# carcomputer2.net
KiCad netlist of a schematic drawn in EAGLE
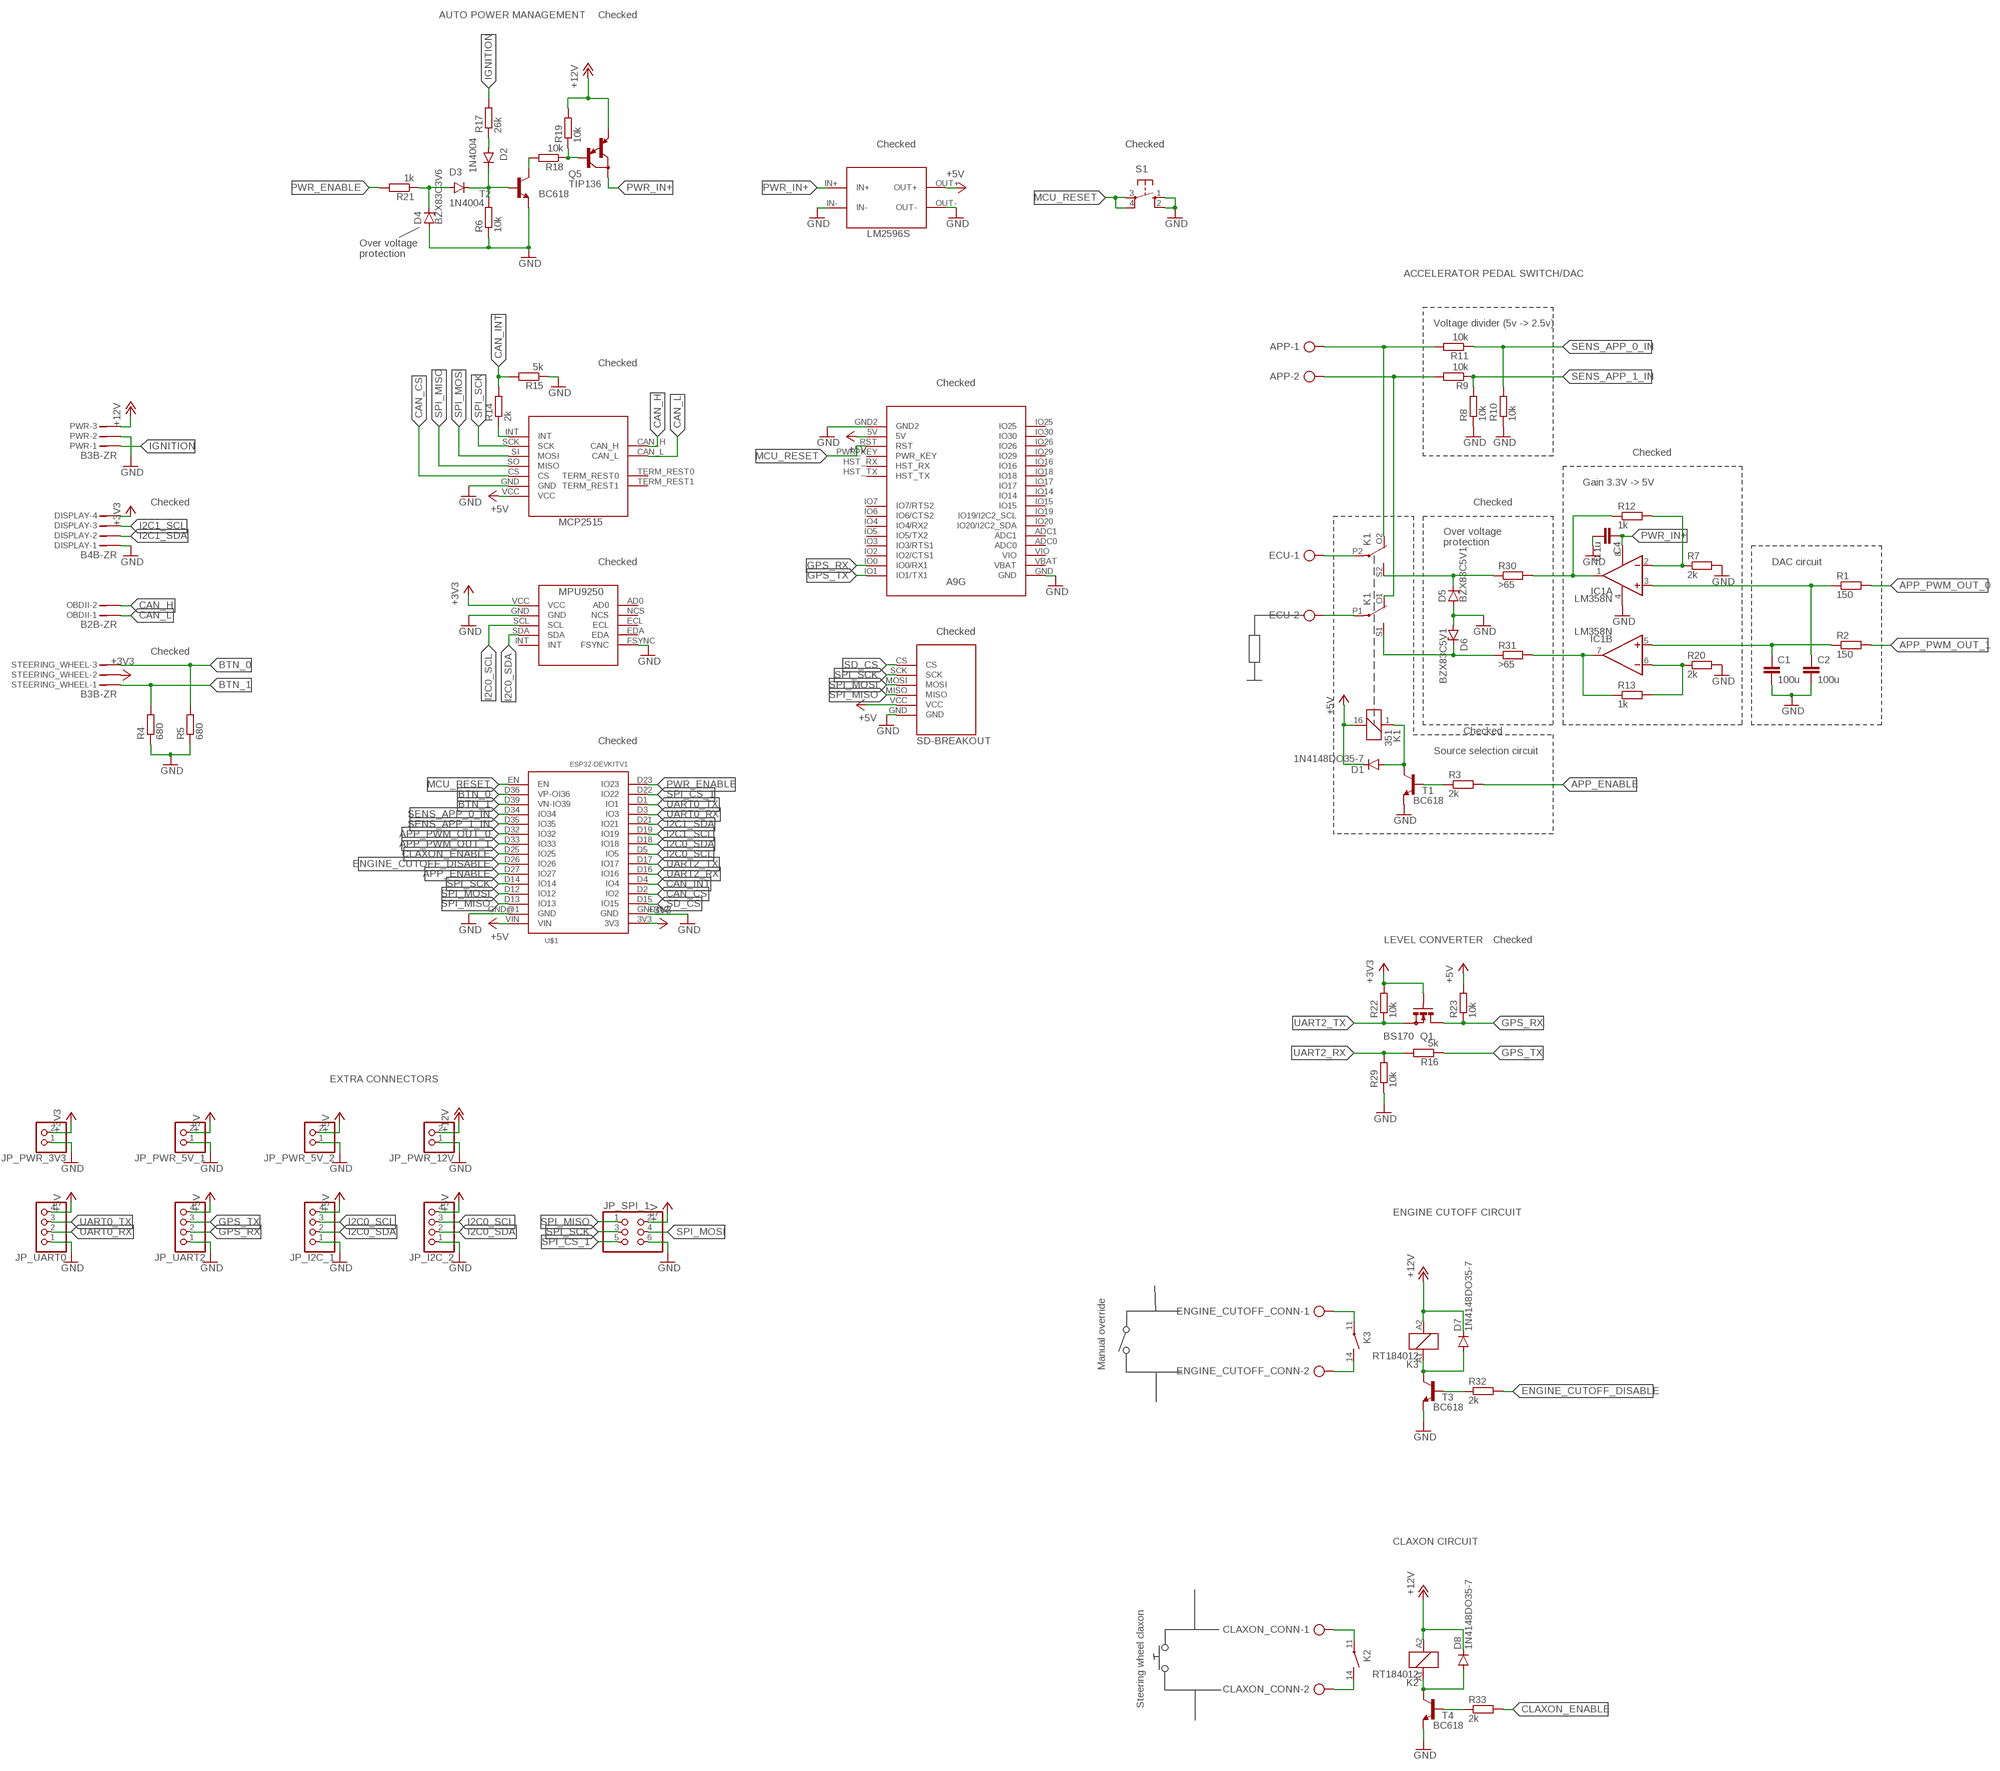
[diagram p0: schematic, sheet 1]

(export (version "E")
  (design (tool "Eeschema 10.0.6"))
  (components
    (comp (ref "APP")
      (value "AK300/2")
      (footprint "eagle-import:AK300_2")
      (libsource (lib "eagle-import") (part "AK300/2"))
    )
    (comp (ref "C1")
      (value "100u")
      (footprint "eagle-import:C025-050X050")
      (libsource (lib "eagle-import") (part "C-EU025-050X050"))
    )
    (comp (ref "C2")
      (value "100u")
      (footprint "eagle-import:C025-050X050")
      (libsource (lib "eagle-import") (part "C-EU025-050X050"))
    )
    (comp (ref "C4")
      (value "0.1u")
      (footprint "eagle-import:C025-050X050")
      (libsource (lib "eagle-import") (part "C-EU025-050X050"))
    )
    (comp (ref "CLAXON_CONN")
      (value "AK300/2")
      (footprint "eagle-import:AK300_2")
      (libsource (lib "eagle-import") (part "AK300/2"))
    )
    (comp (ref "D1")
      (value "1N4148DO35-7")
      (footprint "eagle-import:DO35-7")
      (libsource (lib "eagle-import") (part "1N4148DO35-7"))
    )
    (comp (ref "D2")
      (value "1N4004")
      (footprint "eagle-import:DO41-10")
      (libsource (lib "eagle-import") (part "1N4004"))
    )
    (comp (ref "D3")
      (value "1N4004")
      (footprint "eagle-import:DO41-10")
      (libsource (lib "eagle-import") (part "1N4004"))
    )
    (comp (ref "D4")
      (value "BZX83C3V6")
      (footprint "eagle-import:DO41Z10")
      (libsource (lib "eagle-import") (part "BZX85"))
    )
    (comp (ref "D5")
      (value "BZX83C5V1")
      (footprint "eagle-import:DO41Z10")
      (libsource (lib "eagle-import") (part "BZX85"))
    )
    (comp (ref "D6")
      (value "BZX83C5V1")
      (footprint "eagle-import:DO41Z10")
      (libsource (lib "eagle-import") (part "BZX85"))
    )
    (comp (ref "D7")
      (value "1N4148DO35-7")
      (footprint "eagle-import:DO35-7")
      (libsource (lib "eagle-import") (part "1N4148DO35-7"))
    )
    (comp (ref "D8")
      (value "1N4148DO35-7")
      (footprint "eagle-import:DO35-7")
      (libsource (lib "eagle-import") (part "1N4148DO35-7"))
    )
    (comp (ref "DISPLAY")
      (value "B4B-ZR")
      (footprint "eagle-import:B4B-ZR")
      (fields (field (name "MF") "FARNELL") (field (name "MPN") "B4B-ZR(LF)(SN)"))
      (libsource (lib "eagle-import") (part "?4B-ZRB"))
    )
    (comp (ref "ECU")
      (value "AK300/2")
      (footprint "eagle-import:AK300_2")
      (libsource (lib "eagle-import") (part "AK300/2"))
    )
    (comp (ref "ENGINE_CUTOFF_CONN")
      (value "AK300/2")
      (footprint "eagle-import:AK300_2")
      (libsource (lib "eagle-import") (part "AK300/2"))
    )
    (comp (ref "IC1")
      (value "LM358N")
      (footprint "eagle-import:DIL08")
      (libsource (lib "eagle-import") (part "LM358N"))
    )
    (comp (ref "JP_I2C_1")
      (value "PINHD-1X4")
      (footprint "eagle-import:1X04")
      (libsource (lib "eagle-import") (part "PINHD-1X4"))
    )
    (comp (ref "JP_I2C_2")
      (value "PINHD-1X4")
      (footprint "eagle-import:1X04")
      (libsource (lib "eagle-import") (part "PINHD-1X4"))
    )
    (comp (ref "JP_PWR_3V3")
      (value "PINHD-1X2")
      (footprint "eagle-import:1X02")
      (libsource (lib "eagle-import") (part "PINHD-1X2"))
    )
    (comp (ref "JP_PWR_5V_1")
      (value "PINHD-1X2")
      (footprint "eagle-import:1X02")
      (libsource (lib "eagle-import") (part "PINHD-1X2"))
    )
    (comp (ref "JP_PWR_5V_2")
      (value "PINHD-1X2")
      (footprint "eagle-import:1X02")
      (libsource (lib "eagle-import") (part "PINHD-1X2"))
    )
    (comp (ref "JP_PWR_12V")
      (value "PINHD-1X2")
      (footprint "eagle-import:1X02")
      (libsource (lib "eagle-import") (part "PINHD-1X2"))
    )
    (comp (ref "JP_SPI_1")
      (value "PINHD-2X3")
      (footprint "eagle-import:2X03")
      (libsource (lib "eagle-import") (part "PINHD-2X3"))
    )
    (comp (ref "JP_UART0")
      (value "PINHD-1X4")
      (footprint "eagle-import:1X04")
      (libsource (lib "eagle-import") (part "PINHD-1X4"))
    )
    (comp (ref "JP_UART2")
      (value "PINHD-1X4")
      (footprint "eagle-import:1X04")
      (libsource (lib "eagle-import") (part "PINHD-1X4"))
    )
    (comp (ref "K1")
      (value "351")
      (footprint "eagle-import:351")
      (libsource (lib "eagle-import") (part "351"))
    )
    (comp (ref "K2")
      (value "RT184012")
      (footprint "eagle-import:RT-N_O12A3.5")
      (fields (field (name "MF") "TYCO ELECTRONICS"))
      (libsource (lib "eagle-import") (part "RT?184012"))
    )
    (comp (ref "K3")
      (value "RT184012")
      (footprint "eagle-import:RT-N_O12A3.5")
      (fields (field (name "MF") "TYCO ELECTRONICS"))
      (libsource (lib "eagle-import") (part "RT?184012"))
    )
    (comp (ref "OBDII")
      (value "B2B-ZR")
      (footprint "eagle-import:B2B-ZR")
      (libsource (lib "eagle-import") (part "?2B-ZRB"))
    )
    (comp (ref "PWR")
      (value "B3B-ZR")
      (footprint "eagle-import:B3B-ZR")
      (libsource (lib "eagle-import") (part "?3B-ZRB"))
    )
    (comp (ref "Q1")
      (value "BS170")
      (footprint "eagle-import:SOT54E")
      (libsource (lib "eagle-import") (part "BS170"))
    )
    (comp (ref "Q5")
      (value "TIP136")
      (footprint "eagle-import:TO220")
      (libsource (lib "eagle-import") (part "TIP136"))
    )
    (comp (ref "R1")
      (value "150")
      (footprint "eagle-import:0207_7")
      (libsource (lib "eagle-import") (part "R-EU_0207/7"))
    )
    (comp (ref "R2")
      (value "150")
      (footprint "eagle-import:0207_7")
      (libsource (lib "eagle-import") (part "R-EU_0207/7"))
    )
    (comp (ref "R3")
      (value "2k")
      (footprint "eagle-import:0207_7")
      (libsource (lib "eagle-import") (part "R-EU_0207/7"))
    )
    (comp (ref "R4")
      (value "680")
      (footprint "eagle-import:0207_7")
      (libsource (lib "eagle-import") (part "R-EU_0207/7"))
    )
    (comp (ref "R5")
      (value "680")
      (footprint "eagle-import:0207_7")
      (libsource (lib "eagle-import") (part "R-EU_0207/7"))
    )
    (comp (ref "R6")
      (value "10k")
      (footprint "eagle-import:0207_7")
      (libsource (lib "eagle-import") (part "R-EU_0207/7"))
    )
    (comp (ref "R7")
      (value "2k")
      (footprint "eagle-import:0207_7")
      (libsource (lib "eagle-import") (part "R-EU_0207/7"))
    )
    (comp (ref "R8")
      (value "10k")
      (footprint "eagle-import:0207_7")
      (libsource (lib "eagle-import") (part "R-EU_0207/7"))
    )
    (comp (ref "R9")
      (value "10k")
      (footprint "eagle-import:0207_7")
      (libsource (lib "eagle-import") (part "R-EU_0207/7"))
    )
    (comp (ref "R10")
      (value "10k")
      (footprint "eagle-import:0207_7")
      (libsource (lib "eagle-import") (part "R-EU_0207/7"))
    )
    (comp (ref "R11")
      (value "10k")
      (footprint "eagle-import:0207_7")
      (libsource (lib "eagle-import") (part "R-EU_0207/7"))
    )
    (comp (ref "R12")
      (value "1k")
      (footprint "eagle-import:0207_7")
      (libsource (lib "eagle-import") (part "R-EU_0207/7"))
    )
    (comp (ref "R13")
      (value "1k")
      (footprint "eagle-import:0207_7")
      (libsource (lib "eagle-import") (part "R-EU_0207/7"))
    )
    (comp (ref "R14")
      (value "2k")
      (footprint "eagle-import:0207_7")
      (libsource (lib "eagle-import") (part "R-EU_0207/7"))
    )
    (comp (ref "R15")
      (value "5k")
      (footprint "eagle-import:0207_7")
      (libsource (lib "eagle-import") (part "R-EU_0207/7"))
    )
    (comp (ref "R16")
      (value "5k")
      (footprint "eagle-import:0207_7")
      (libsource (lib "eagle-import") (part "R-EU_0207/7"))
    )
    (comp (ref "R17")
      (value "26k")
      (footprint "eagle-import:0207_7")
      (libsource (lib "eagle-import") (part "R-EU_0207/7"))
    )
    (comp (ref "R18")
      (value "10k")
      (footprint "eagle-import:0207_7")
      (libsource (lib "eagle-import") (part "R-EU_0207/7"))
    )
    (comp (ref "R19")
      (value "10k")
      (footprint "eagle-import:0207_7")
      (libsource (lib "eagle-import") (part "R-EU_0207/7"))
    )
    (comp (ref "R20")
      (value "2k")
      (footprint "eagle-import:0207_7")
      (libsource (lib "eagle-import") (part "R-EU_0207/7"))
    )
    (comp (ref "R21")
      (value "1k")
      (footprint "eagle-import:0207_7")
      (libsource (lib "eagle-import") (part "R-EU_0207/7"))
    )
    (comp (ref "R22")
      (value "10k")
      (footprint "eagle-import:0207_7")
      (libsource (lib "eagle-import") (part "R-EU_0207/7"))
    )
    (comp (ref "R23")
      (value "10k")
      (footprint "eagle-import:0207_7")
      (libsource (lib "eagle-import") (part "R-EU_0207/7"))
    )
    (comp (ref "R29")
      (value "10k")
      (footprint "eagle-import:0207_7")
      (libsource (lib "eagle-import") (part "R-EU_0207/7"))
    )
    (comp (ref "R30")
      (value ">65")
      (footprint "eagle-import:0207_7")
      (libsource (lib "eagle-import") (part "R-EU_0207/7"))
    )
    (comp (ref "R31")
      (value ">65")
      (footprint "eagle-import:0207_7")
      (libsource (lib "eagle-import") (part "R-EU_0207/7"))
    )
    (comp (ref "R32")
      (value "2k")
      (footprint "eagle-import:0207_7")
      (libsource (lib "eagle-import") (part "R-EU_0207/7"))
    )
    (comp (ref "R33")
      (value "2k")
      (footprint "eagle-import:0207_7")
      (libsource (lib "eagle-import") (part "R-EU_0207/7"))
    )
    (comp (ref "S1")
      (value "10-XX")
      (footprint "eagle-import:B3F-10XX")
      (fields (field (name "MPN") "B3F-1000"))
      (libsource (lib "eagle-import") (part "10-XX"))
    )
    (comp (ref "STEERING_WHEEL")
      (value "B3B-ZR")
      (footprint "eagle-import:B3B-ZR")
      (libsource (lib "eagle-import") (part "?3B-ZRB"))
    )
    (comp (ref "T1")
      (value "BC618")
      (footprint "eagle-import:TO92-EBC")
      (libsource (lib "eagle-import") (part "BC618"))
    )
    (comp (ref "T2")
      (value "BC618")
      (footprint "eagle-import:TO92-EBC")
      (libsource (lib "eagle-import") (part "BC618"))
    )
    (comp (ref "T3")
      (value "BC618")
      (footprint "eagle-import:TO92-EBC")
      (libsource (lib "eagle-import") (part "BC618"))
    )
    (comp (ref "T4")
      (value "BC618")
      (footprint "eagle-import:TO92-EBC")
      (libsource (lib "eagle-import") (part "BC618"))
    )
    (comp (ref "U$1")
      (value "ESP32DEVKITV1")
      (footprint "eagle-import:ESP32-DEVKITV1")
      (libsource (lib "eagle-import") (part "ESP32DEVKITV1"))
    )
    (comp (ref "U$2")
      (value "MCP2515_DEVBOARDINVERTED")
      (footprint "eagle-import:MCP2515_DEVBOARD_INVERTED")
      (libsource (lib "eagle-import") (part "MCP2515_DEVBOARDINVERTED"))
    )
    (comp (ref "U$3")
      (value "MPU9250_BREAKOUT")
      (footprint "eagle-import:MPU9250_BREAKOUT")
      (libsource (lib "eagle-import") (part "MPU9250_BREAKOUT"))
    )
    (comp (ref "U$4")
      (value "LM2596S")
      (footprint "eagle-import:LM2596S")
      (libsource (lib "eagle-import") (part "LM2596S"))
    )
    (comp (ref "U$5")
      (value "HKD-MICRO-SD-BREAKOUT")
      (footprint "eagle-import:HKD-MICRO-SD-BREAKOUT")
      (libsource (lib "eagle-import") (part "HKD-MICRO-SD-BREAKOUT"))
    )
    (comp (ref "U$6")
      (value "A9G")
      (footprint "eagle-import:A9G")
      (libsource (lib "eagle-import") (part "A9G"))
    )
  )
  (nets
    (net (code "1") (name "+3V3") (class "Default")
      (node (ref "DISPLAY") (pin "4") (pinfunction "1_4") (pintype "passive"))
      (node (ref "JP_PWR_3V3") (pin "2") (pinfunction "2_2") (pintype "passive"))
      (node (ref "Q1") (pin "G") (pinfunction "G_G") (pintype "passive"))
      (node (ref "R22") (pin "2") (pinfunction "2_2") (pintype "passive"))
      (node (ref "STEERING_WHEEL") (pin "2") (pinfunction "1_2") (pintype "passive"))
      (node (ref "U$1") (pin "3V3") (pinfunction "3V3_3V3") (pintype "bidirectional"))
      (node (ref "U$3") (pin "VCC") (pinfunction "VCC_VCC") (pintype "bidirectional"))
    )
    (net (code "2") (name "+5V") (class "Default")
      (node (ref "D1") (pin "C") (pinfunction "C_C") (pintype "passive"))
      (node (ref "JP_I2C_1") (pin "4") (pinfunction "4_4") (pintype "passive"))
      (node (ref "JP_I2C_2") (pin "4") (pinfunction "4_4") (pintype "passive"))
      (node (ref "JP_PWR_5V_1") (pin "2") (pinfunction "2_2") (pintype "passive"))
      (node (ref "JP_PWR_5V_2") (pin "2") (pinfunction "2_2") (pintype "passive"))
      (node (ref "JP_SPI_1") (pin "2") (pinfunction "2_2") (pintype "passive"))
      (node (ref "JP_UART0") (pin "4") (pinfunction "4_4") (pintype "passive"))
      (node (ref "JP_UART2") (pin "4") (pinfunction "4_4") (pintype "passive"))
      (node (ref "K1") (pin "16") (pinfunction "2_16") (pintype "passive"))
      (node (ref "R23") (pin "2") (pinfunction "2_2") (pintype "passive"))
      (node (ref "U$1") (pin "VIN") (pinfunction "VIN_VIN") (pintype "bidirectional"))
      (node (ref "U$2") (pin "VCC") (pinfunction "VCC_VCC") (pintype "bidirectional"))
      (node (ref "U$4") (pin "OUT+") (pinfunction "OUT+_OUT+") (pintype "bidirectional"))
      (node (ref "U$5") (pin "VCC") (pinfunction "VCC_VCC") (pintype "bidirectional"))
      (node (ref "U$6") (pin "5V") (pinfunction "5V_5V") (pintype "bidirectional"))
    )
    (net (code "3") (name "+12V") (class "Default")
      (node (ref "D7") (pin "C") (pinfunction "C_C") (pintype "passive"))
      (node (ref "D8") (pin "C") (pinfunction "C_C") (pintype "passive"))
      (node (ref "JP_PWR_12V") (pin "2") (pinfunction "2_2") (pintype "passive"))
      (node (ref "K2") (pin "A2") (pinfunction "2_A2") (pintype "passive"))
      (node (ref "K3") (pin "A2") (pinfunction "2_A2") (pintype "passive"))
      (node (ref "PWR") (pin "3") (pinfunction "1_3") (pintype "passive"))
      (node (ref "Q5") (pin "3") (pinfunction "E_3") (pintype "passive"))
      (node (ref "R19") (pin "2") (pinfunction "2_2") (pintype "passive"))
    )
    (net (code "4") (name "APP_ENABLE") (class "Default")
      (node (ref "R3") (pin "2") (pinfunction "2_2") (pintype "passive"))
      (node (ref "U$1") (pin "D27") (pinfunction "IO27_D27") (pintype "bidirectional"))
    )
    (net (code "5") (name "APP_PWM_OUT_0") (class "Default")
      (node (ref "R1") (pin "2") (pinfunction "2_2") (pintype "passive"))
      (node (ref "U$1") (pin "D32") (pinfunction "IO32_D32") (pintype "bidirectional"))
    )
    (net (code "6") (name "APP_PWM_OUT_1") (class "Default")
      (node (ref "R2") (pin "2") (pinfunction "2_2") (pintype "passive"))
      (node (ref "U$1") (pin "D33") (pinfunction "IO33_D33") (pintype "bidirectional"))
    )
    (net (code "7") (name "BTN_0") (class "Default")
      (node (ref "R5") (pin "2") (pinfunction "2_2") (pintype "passive"))
      (node (ref "STEERING_WHEEL") (pin "3") (pinfunction "1_3") (pintype "passive"))
      (node (ref "U$1") (pin "D36") (pinfunction "VP-OI36_D36") (pintype "bidirectional"))
    )
    (net (code "8") (name "BTN_1") (class "Default")
      (node (ref "R4") (pin "2") (pinfunction "2_2") (pintype "passive"))
      (node (ref "STEERING_WHEEL") (pin "1") (pinfunction "1_1") (pintype "passive"))
      (node (ref "U$1") (pin "D39") (pinfunction "VN-IO39_D39") (pintype "bidirectional"))
    )
    (net (code "9") (name "CAN_CS") (class "Default")
      (node (ref "U$1") (pin "D2") (pinfunction "IO2_D2") (pintype "bidirectional"))
      (node (ref "U$2") (pin "CS") (pinfunction "CS_CS") (pintype "input"))
    )
    (net (code "10") (name "CAN_H") (class "Default")
      (node (ref "OBDII") (pin "2") (pinfunction "1_2") (pintype "passive"))
      (node (ref "U$2") (pin "CAN_H") (pinfunction "CAN_H_CAN_H") (pintype "bidirectional"))
    )
    (net (code "11") (name "CAN_INT") (class "Default")
      (node (ref "R14") (pin "2") (pinfunction "2_2") (pintype "passive"))
      (node (ref "R15") (pin "2") (pinfunction "2_2") (pintype "passive"))
      (node (ref "U$1") (pin "D4") (pinfunction "IO4_D4") (pintype "bidirectional"))
    )
    (net (code "12") (name "CAN_L") (class "Default")
      (node (ref "OBDII") (pin "1") (pinfunction "1_1") (pintype "passive"))
      (node (ref "U$2") (pin "CAN_L") (pinfunction "CAN_L_CAN_L") (pintype "bidirectional"))
    )
    (net (code "13") (name "CLAXON_ENABLE") (class "Default")
      (node (ref "R33") (pin "2") (pinfunction "2_2") (pintype "passive"))
      (node (ref "U$1") (pin "D25") (pinfunction "IO25_D25") (pintype "bidirectional"))
    )
    (net (code "14") (name "ENGINE_CUTOFF_DISABLE") (class "Default")
      (node (ref "R32") (pin "2") (pinfunction "2_2") (pintype "passive"))
      (node (ref "U$1") (pin "D26") (pinfunction "IO26_D26") (pintype "bidirectional"))
    )
    (net (code "15") (name "GND") (class "Default")
      (node (ref "C1") (pin "2") (pinfunction "2_2") (pintype "passive"))
      (node (ref "C2") (pin "2") (pinfunction "2_2") (pintype "passive"))
      (node (ref "C4") (pin "2") (pinfunction "2_2") (pintype "passive"))
      (node (ref "D4") (pin "A") (pinfunction "A_A") (pintype "passive"))
      (node (ref "D5") (pin "A") (pinfunction "A_A") (pintype "passive"))
      (node (ref "D6") (pin "A") (pinfunction "A_A") (pintype "passive"))
      (node (ref "DISPLAY") (pin "1") (pinfunction "1_1") (pintype "passive"))
      (node (ref "IC1") (pin "4") (pinfunction "V-_4") (pintype "power_in"))
      (node (ref "JP_I2C_1") (pin "1") (pinfunction "1_1") (pintype "passive"))
      (node (ref "JP_I2C_2") (pin "1") (pinfunction "1_1") (pintype "passive"))
      (node (ref "JP_PWR_12V") (pin "1") (pinfunction "1_1") (pintype "passive"))
      (node (ref "JP_PWR_3V3") (pin "1") (pinfunction "1_1") (pintype "passive"))
      (node (ref "JP_PWR_5V_1") (pin "1") (pinfunction "1_1") (pintype "passive"))
      (node (ref "JP_PWR_5V_2") (pin "1") (pinfunction "1_1") (pintype "passive"))
      (node (ref "JP_SPI_1") (pin "6") (pinfunction "6_6") (pintype "passive"))
      (node (ref "JP_UART0") (pin "1") (pinfunction "1_1") (pintype "passive"))
      (node (ref "JP_UART2") (pin "1") (pinfunction "1_1") (pintype "passive"))
      (node (ref "PWR") (pin "2") (pinfunction "1_2") (pintype "passive"))
      (node (ref "R10") (pin "1") (pinfunction "1_1") (pintype "passive"))
      (node (ref "R15") (pin "1") (pinfunction "1_1") (pintype "passive"))
      (node (ref "R20") (pin "2") (pinfunction "2_2") (pintype "passive"))
      (node (ref "R29") (pin "1") (pinfunction "1_1") (pintype "passive"))
      (node (ref "R4") (pin "1") (pinfunction "1_1") (pintype "passive"))
      (node (ref "R5") (pin "1") (pinfunction "1_1") (pintype "passive"))
      (node (ref "R6") (pin "1") (pinfunction "1_1") (pintype "passive"))
      (node (ref "R7") (pin "2") (pinfunction "2_2") (pintype "passive"))
      (node (ref "R8") (pin "1") (pinfunction "1_1") (pintype "passive"))
      (node (ref "S1") (pin "1") (pinfunction "S_1") (pintype "passive"))
      (node (ref "S1") (pin "2") (pinfunction "S1_2") (pintype "passive"))
      (node (ref "T1") (pin "E") (pinfunction "E_E") (pintype "passive"))
      (node (ref "T2") (pin "E") (pinfunction "E_E") (pintype "passive"))
      (node (ref "T3") (pin "E") (pinfunction "E_E") (pintype "passive"))
      (node (ref "T4") (pin "E") (pinfunction "E_E") (pintype "passive"))
      (node (ref "U$1") (pin "GND@1") (pinfunction "GND_GND@1") (pintype "bidirectional"))
      (node (ref "U$1") (pin "GND@2") (pinfunction "GND_GND@2") (pintype "bidirectional"))
      (node (ref "U$2") (pin "GND") (pinfunction "GND_GND") (pintype "bidirectional"))
      (node (ref "U$3") (pin "FSYNC") (pinfunction "FSYNC_FSYNC") (pintype "bidirectional"))
      (node (ref "U$3") (pin "GND") (pinfunction "GND_GND") (pintype "bidirectional"))
      (node (ref "U$4") (pin "IN-") (pinfunction "IN-_IN-") (pintype "bidirectional"))
      (node (ref "U$4") (pin "OUT-") (pinfunction "OUT-_OUT-") (pintype "bidirectional"))
      (node (ref "U$5") (pin "GND") (pinfunction "GND_GND") (pintype "bidirectional"))
      (node (ref "U$6") (pin "GND") (pinfunction "GND_GND") (pintype "bidirectional"))
      (node (ref "U$6") (pin "GND2") (pinfunction "GND2_GND2") (pintype "bidirectional"))
    )
    (net (code "16") (name "GPS_RX") (class "Default")
      (node (ref "JP_UART2") (pin "2") (pinfunction "2_2") (pintype "passive"))
      (node (ref "Q1") (pin "D") (pinfunction "D_D") (pintype "passive"))
      (node (ref "R23") (pin "1") (pinfunction "1_1") (pintype "passive"))
      (node (ref "U$6") (pin "IO0") (pinfunction "IO0/RX1_IO0") (pintype "bidirectional"))
    )
    (net (code "17") (name "GPS_TX") (class "Default")
      (node (ref "JP_UART2") (pin "3") (pinfunction "3_3") (pintype "passive"))
      (node (ref "R16") (pin "1") (pinfunction "1_1") (pintype "passive"))
      (node (ref "U$6") (pin "IO1") (pinfunction "IO1/TX1_IO1") (pintype "bidirectional"))
    )
    (net (code "18") (name "I2C0_SCL") (class "Default")
      (node (ref "JP_I2C_1") (pin "3") (pinfunction "3_3") (pintype "passive"))
      (node (ref "JP_I2C_2") (pin "3") (pinfunction "3_3") (pintype "passive"))
      (node (ref "U$1") (pin "D5") (pinfunction "IO5_D5") (pintype "bidirectional"))
      (node (ref "U$3") (pin "SCL") (pinfunction "SCL_SCL") (pintype "bidirectional"))
    )
    (net (code "19") (name "I2C0_SDA") (class "Default")
      (node (ref "JP_I2C_1") (pin "2") (pinfunction "2_2") (pintype "passive"))
      (node (ref "JP_I2C_2") (pin "2") (pinfunction "2_2") (pintype "passive"))
      (node (ref "U$1") (pin "D18") (pinfunction "IO18_D18") (pintype "bidirectional"))
      (node (ref "U$3") (pin "SDA") (pinfunction "SDA_SDA") (pintype "bidirectional"))
    )
    (net (code "20") (name "I2C1_SCL") (class "Default")
      (node (ref "DISPLAY") (pin "3") (pinfunction "1_3") (pintype "passive"))
      (node (ref "U$1") (pin "D19") (pinfunction "IO19_D19") (pintype "bidirectional"))
    )
    (net (code "21") (name "I2C1_SDA") (class "Default")
      (node (ref "DISPLAY") (pin "2") (pinfunction "1_2") (pintype "passive"))
      (node (ref "U$1") (pin "D21") (pinfunction "IO21_D21") (pintype "bidirectional"))
    )
    (net (code "22") (name "IGNITION") (class "Default")
      (node (ref "PWR") (pin "1") (pinfunction "1_1") (pintype "passive"))
      (node (ref "R17") (pin "2") (pinfunction "2_2") (pintype "passive"))
    )
    (net (code "23") (name "MCU_RESET") (class "Default")
      (node (ref "S1") (pin "3") (pinfunction "P_3") (pintype "passive"))
      (node (ref "S1") (pin "4") (pinfunction "P1_4") (pintype "passive"))
      (node (ref "U$1") (pin "EN") (pinfunction "EN_EN") (pintype "bidirectional"))
      (node (ref "U$6") (pin "RST") (pinfunction "RST_RST") (pintype "bidirectional"))
    )
    (net (code "24") (name "Net-(APPA-KL)") (class "Default")
      (node (ref "APP") (pin "1") (pinfunction "KL_1") (pintype "passive"))
      (node (ref "K1") (pin "O2") (pinfunction "O_O2") (pintype "passive"))
      (node (ref "R11") (pin "2") (pinfunction "2_2") (pintype "passive"))
    )
    (net (code "25") (name "Net-(APPB-KL)") (class "Default")
      (node (ref "APP") (pin "2") (pinfunction "KL_2") (pintype "passive"))
      (node (ref "K1") (pin "O1") (pinfunction "O_O1") (pintype "passive"))
      (node (ref "R9") (pin "2") (pinfunction "2_2") (pintype "passive"))
    )
    (net (code "26") (name "Net-(CLAXON_CONNA-KL)") (class "Default")
      (node (ref "CLAXON_CONN") (pin "1") (pinfunction "KL_1") (pintype "passive"))
      (node (ref "K2") (pin "11") (pinfunction "P_11") (pintype "passive"))
    )
    (net (code "27") (name "Net-(CLAXON_CONNB-KL)") (class "Default")
      (node (ref "CLAXON_CONN") (pin "2") (pinfunction "KL_2") (pintype "passive"))
      (node (ref "K2") (pin "14") (pinfunction "S_14") (pintype "passive"))
    )
    (net (code "28") (name "Net-(D1-PadA)") (class "Default")
      (node (ref "D1") (pin "A") (pinfunction "A_A") (pintype "passive"))
      (node (ref "K1") (pin "1") (pinfunction "1_1") (pintype "passive"))
      (node (ref "T1") (pin "C") (pinfunction "C_C") (pintype "passive"))
    )
    (net (code "29") (name "Net-(D2-PadA)") (class "Default")
      (node (ref "D2") (pin "A") (pinfunction "A_A") (pintype "passive"))
      (node (ref "R17") (pin "1") (pinfunction "1_1") (pintype "passive"))
    )
    (net (code "30") (name "Net-(D2-PadC)") (class "Default")
      (node (ref "D2") (pin "C") (pinfunction "C_C") (pintype "passive"))
      (node (ref "D3") (pin "C") (pinfunction "C_C") (pintype "passive"))
      (node (ref "R6") (pin "2") (pinfunction "2_2") (pintype "passive"))
      (node (ref "T2") (pin "B") (pinfunction "B_B") (pintype "passive"))
    )
    (net (code "31") (name "Net-(D3-PadA)") (class "Default")
      (node (ref "D3") (pin "A") (pinfunction "A_A") (pintype "passive"))
      (node (ref "D4") (pin "C") (pinfunction "C_C") (pintype "passive"))
      (node (ref "R21") (pin "1") (pinfunction "1_1") (pintype "passive"))
    )
    (net (code "32") (name "Net-(ECUA-KL)") (class "Default")
      (node (ref "ECU") (pin "1") (pinfunction "KL_1") (pintype "passive"))
      (node (ref "K1") (pin "P2") (pinfunction "P_P2") (pintype "passive"))
    )
    (net (code "33") (name "Net-(ECUB-KL)") (class "Default")
      (node (ref "ECU") (pin "2") (pinfunction "KL_2") (pintype "passive"))
      (node (ref "K1") (pin "P1") (pinfunction "P_P1") (pintype "passive"))
    )
    (net (code "34") (name "Net-(ENGINE_CUTOFF_CONNA-KL)") (class "Default")
      (node (ref "ENGINE_CUTOFF_CONN") (pin "1") (pinfunction "KL_1") (pintype "passive"))
      (node (ref "K3") (pin "11") (pinfunction "P_11") (pintype "passive"))
    )
    (net (code "35") (name "Net-(ENGINE_CUTOFF_CONNB-KL)") (class "Default")
      (node (ref "ENGINE_CUTOFF_CONN") (pin "2") (pinfunction "KL_2") (pintype "passive"))
      (node (ref "K3") (pin "14") (pinfunction "S_14") (pintype "passive"))
    )
    (net (code "36") (name "Net-(IC1A-+IN)") (class "Default")
      (node (ref "C2") (pin "1") (pinfunction "1_1") (pintype "passive"))
      (node (ref "IC1") (pin "3") (pinfunction "+IN_3") (pintype "input"))
      (node (ref "R1") (pin "1") (pinfunction "1_1") (pintype "passive"))
    )
    (net (code "37") (name "Net-(IC1A--IN)") (class "Default")
      (node (ref "IC1") (pin "2") (pinfunction "-IN_2") (pintype "input"))
      (node (ref "R12") (pin "2") (pinfunction "2_2") (pintype "passive"))
      (node (ref "R7") (pin "1") (pinfunction "1_1") (pintype "passive"))
    )
    (net (code "38") (name "Net-(IC1A-OUT)") (class "Default")
      (node (ref "IC1") (pin "1") (pinfunction "OUT_1") (pintype "output"))
      (node (ref "R12") (pin "1") (pinfunction "1_1") (pintype "passive"))
      (node (ref "R30") (pin "2") (pinfunction "2_2") (pintype "passive"))
    )
    (net (code "39") (name "Net-(IC1B-+IN)") (class "Default")
      (node (ref "C1") (pin "1") (pinfunction "1_1") (pintype "passive"))
      (node (ref "IC1") (pin "5") (pinfunction "+IN_5") (pintype "input"))
      (node (ref "R2") (pin "1") (pinfunction "1_1") (pintype "passive"))
    )
    (net (code "40") (name "Net-(IC1B--IN)") (class "Default")
      (node (ref "IC1") (pin "6") (pinfunction "-IN_6") (pintype "input"))
      (node (ref "R13") (pin "2") (pinfunction "2_2") (pintype "passive"))
      (node (ref "R20") (pin "1") (pinfunction "1_1") (pintype "passive"))
    )
    (net (code "41") (name "Net-(IC1B-OUT)") (class "Default")
      (node (ref "IC1") (pin "7") (pinfunction "OUT_7") (pintype "output"))
      (node (ref "R13") (pin "1") (pinfunction "1_1") (pintype "passive"))
      (node (ref "R31") (pin "2") (pinfunction "2_2") (pintype "passive"))
    )
    (net (code "42") (name "Net-(K1B-S)") (class "Default")
      (node (ref "D6") (pin "C") (pinfunction "C_C") (pintype "passive"))
      (node (ref "K1") (pin "S1") (pinfunction "S_S1") (pintype "passive"))
      (node (ref "R31") (pin "1") (pinfunction "1_1") (pintype "passive"))
    )
    (net (code "43") (name "Net-(K1C-S)") (class "Default")
      (node (ref "D5") (pin "C") (pinfunction "C_C") (pintype "passive"))
      (node (ref "K1") (pin "S2") (pinfunction "S_S2") (pintype "passive"))
      (node (ref "R30") (pin "1") (pinfunction "1_1") (pintype "passive"))
    )
    (net (code "44") (name "Net-(K2A-1)") (class "Default")
      (node (ref "D8") (pin "A") (pinfunction "A_A") (pintype "passive"))
      (node (ref "K2") (pin "A1") (pinfunction "1_A1") (pintype "passive"))
      (node (ref "T4") (pin "C") (pinfunction "C_C") (pintype "passive"))
    )
    (net (code "45") (name "Net-(K3A-1)") (class "Default")
      (node (ref "D7") (pin "A") (pinfunction "A_A") (pintype "passive"))
      (node (ref "K3") (pin "A1") (pinfunction "1_A1") (pintype "passive"))
      (node (ref "T3") (pin "C") (pinfunction "C_C") (pintype "passive"))
    )
    (net (code "46") (name "Net-(Q5-B)") (class "Default")
      (node (ref "Q5") (pin "1") (pinfunction "B_1") (pintype "passive"))
      (node (ref "R18") (pin "1") (pinfunction "1_1") (pintype "passive"))
      (node (ref "R19") (pin "1") (pinfunction "1_1") (pintype "passive"))
    )
    (net (code "47") (name "Net-(R3-Pad1)") (class "Default")
      (node (ref "R3") (pin "1") (pinfunction "1_1") (pintype "passive"))
      (node (ref "T1") (pin "B") (pinfunction "B_B") (pintype "passive"))
    )
    (net (code "48") (name "Net-(R14-Pad1)") (class "Default")
      (node (ref "R14") (pin "1") (pinfunction "1_1") (pintype "passive"))
      (node (ref "U$2") (pin "INT") (pinfunction "INT_INT") (pintype "output"))
    )
    (net (code "49") (name "Net-(R18-Pad2)") (class "Default")
      (node (ref "R18") (pin "2") (pinfunction "2_2") (pintype "passive"))
      (node (ref "T2") (pin "C") (pinfunction "C_C") (pintype "passive"))
    )
    (net (code "50") (name "Net-(R32-Pad1)") (class "Default")
      (node (ref "R32") (pin "1") (pinfunction "1_1") (pintype "passive"))
      (node (ref "T3") (pin "B") (pinfunction "B_B") (pintype "passive"))
    )
    (net (code "51") (name "Net-(R33-Pad1)") (class "Default")
      (node (ref "R33") (pin "1") (pinfunction "1_1") (pintype "passive"))
      (node (ref "T4") (pin "B") (pinfunction "B_B") (pintype "passive"))
    )
    (net (code "52") (name "PWR_ENABLE") (class "Default")
      (node (ref "R21") (pin "2") (pinfunction "2_2") (pintype "passive"))
      (node (ref "U$1") (pin "D23") (pinfunction "IO23_D23") (pintype "bidirectional"))
    )
    (net (code "53") (name "PWR_IN+") (class "Default")
      (node (ref "C4") (pin "1") (pinfunction "1_1") (pintype "passive"))
      (node (ref "IC1") (pin "8") (pinfunction "V+_8") (pintype "power_in"))
      (node (ref "Q5") (pin "2") (pinfunction "C_2") (pintype "passive"))
      (node (ref "U$4") (pin "IN+") (pinfunction "IN+_IN+") (pintype "bidirectional"))
    )
    (net (code "54") (name "SD_CS") (class "Default")
      (node (ref "U$1") (pin "D15") (pinfunction "IO15_D15") (pintype "bidirectional"))
      (node (ref "U$5") (pin "CS") (pinfunction "CS_CS") (pintype "bidirectional"))
    )
    (net (code "55") (name "SENS_APP_0_IN") (class "Default")
      (node (ref "R10") (pin "2") (pinfunction "2_2") (pintype "passive"))
      (node (ref "R11") (pin "1") (pinfunction "1_1") (pintype "passive"))
      (node (ref "U$1") (pin "D34") (pinfunction "IO34_D34") (pintype "bidirectional"))
    )
    (net (code "56") (name "SENS_APP_1_IN") (class "Default")
      (node (ref "R8") (pin "2") (pinfunction "2_2") (pintype "passive"))
      (node (ref "R9") (pin "1") (pinfunction "1_1") (pintype "passive"))
      (node (ref "U$1") (pin "D35") (pinfunction "IO35_D35") (pintype "bidirectional"))
    )
    (net (code "57") (name "SPI_CS_1") (class "Default")
      (node (ref "JP_SPI_1") (pin "5") (pinfunction "5_5") (pintype "passive"))
      (node (ref "U$1") (pin "D22") (pinfunction "IO22_D22") (pintype "bidirectional"))
    )
    (net (code "58") (name "SPI_MISO") (class "Default")
      (node (ref "JP_SPI_1") (pin "1") (pinfunction "1_1") (pintype "passive"))
      (node (ref "U$1") (pin "D13") (pinfunction "IO13_D13") (pintype "bidirectional"))
      (node (ref "U$2") (pin "SO") (pinfunction "MISO_SO") (pintype "output"))
      (node (ref "U$5") (pin "MISO") (pinfunction "MISO_MISO") (pintype "bidirectional"))
    )
    (net (code "59") (name "SPI_MOSI") (class "Default")
      (node (ref "JP_SPI_1") (pin "4") (pinfunction "4_4") (pintype "passive"))
      (node (ref "U$1") (pin "D12") (pinfunction "IO12_D12") (pintype "bidirectional"))
      (node (ref "U$2") (pin "SI") (pinfunction "MOSI_SI") (pintype "input"))
      (node (ref "U$5") (pin "MOSI") (pinfunction "MOSI_MOSI") (pintype "bidirectional"))
    )
    (net (code "60") (name "SPI_SCK") (class "Default")
      (node (ref "JP_SPI_1") (pin "3") (pinfunction "3_3") (pintype "passive"))
      (node (ref "U$1") (pin "D14") (pinfunction "IO14_D14") (pintype "bidirectional"))
      (node (ref "U$2") (pin "SCK") (pinfunction "SCK_SCK") (pintype "input"))
      (node (ref "U$5") (pin "SCK") (pinfunction "SCK_SCK") (pintype "bidirectional"))
    )
    (net (code "61") (name "UART0_RX") (class "Default")
      (node (ref "JP_UART0") (pin "2") (pinfunction "2_2") (pintype "passive"))
      (node (ref "U$1") (pin "D3") (pinfunction "IO3_D3") (pintype "bidirectional"))
    )
    (net (code "62") (name "UART0_TX") (class "Default")
      (node (ref "JP_UART0") (pin "3") (pinfunction "3_3") (pintype "passive"))
      (node (ref "U$1") (pin "D1") (pinfunction "IO1_D1") (pintype "bidirectional"))
    )
    (net (code "63") (name "UART2_RX") (class "Default")
      (node (ref "R16") (pin "2") (pinfunction "2_2") (pintype "passive"))
      (node (ref "R29") (pin "2") (pinfunction "2_2") (pintype "passive"))
      (node (ref "U$1") (pin "D16") (pinfunction "IO16_D16") (pintype "bidirectional"))
    )
    (net (code "64") (name "UART2_TX") (class "Default")
      (node (ref "Q1") (pin "S") (pinfunction "S_S") (pintype "passive"))
      (node (ref "R22") (pin "1") (pinfunction "1_1") (pintype "passive"))
      (node (ref "U$1") (pin "D17") (pinfunction "IO17_D17") (pintype "bidirectional"))
    )
    (net (code "65") (name "unconnected-(U$2-PadTERM_REST0)") (class "Default")
      (node (ref "U$2") (pin "TERM_REST0") (pinfunction "TERM_REST0_TERM_REST0") (pintype "bidirectional"))
    )
    (net (code "66") (name "unconnected-(U$2-PadTERM_REST1)") (class "Default")
      (node (ref "U$2") (pin "TERM_REST1") (pinfunction "TERM_REST1_TERM_REST1") (pintype "bidirectional"))
    )
    (net (code "67") (name "unconnected-(U$3-PadAD0)") (class "Default")
      (node (ref "U$3") (pin "AD0") (pinfunction "AD0_AD0") (pintype "bidirectional"))
    )
    (net (code "68") (name "unconnected-(U$3-PadECL)") (class "Default")
      (node (ref "U$3") (pin "ECL") (pinfunction "ECL_ECL") (pintype "bidirectional"))
    )
    (net (code "69") (name "unconnected-(U$3-PadEDA)") (class "Default")
      (node (ref "U$3") (pin "EDA") (pinfunction "EDA_EDA") (pintype "bidirectional"))
    )
    (net (code "70") (name "unconnected-(U$3-PadINT)") (class "Default")
      (node (ref "U$3") (pin "INT") (pinfunction "INT_INT") (pintype "bidirectional"))
    )
    (net (code "71") (name "unconnected-(U$3-PadNCS)") (class "Default")
      (node (ref "U$3") (pin "NCS") (pinfunction "NCS_NCS") (pintype "bidirectional"))
    )
    (net (code "72") (name "unconnected-(U$6-IO2{slash}CTS1-PadIO2)") (class "Default")
      (node (ref "U$6") (pin "IO2") (pinfunction "IO2/CTS1_IO2") (pintype "bidirectional"))
    )
    (net (code "73") (name "unconnected-(U$6-IO3{slash}RTS1-PadIO3)") (class "Default")
      (node (ref "U$6") (pin "IO3") (pinfunction "IO3/RTS1_IO3") (pintype "bidirectional"))
    )
    (net (code "74") (name "unconnected-(U$6-IO4{slash}RX2-PadIO4)") (class "Default")
      (node (ref "U$6") (pin "IO4") (pinfunction "IO4/RX2_IO4") (pintype "bidirectional"))
    )
    (net (code "75") (name "unconnected-(U$6-IO5{slash}TX2-PadIO5)") (class "Default")
      (node (ref "U$6") (pin "IO5") (pinfunction "IO5/TX2_IO5") (pintype "bidirectional"))
    )
    (net (code "76") (name "unconnected-(U$6-IO6{slash}CTS2-PadIO6)") (class "Default")
      (node (ref "U$6") (pin "IO6") (pinfunction "IO6/CTS2_IO6") (pintype "bidirectional"))
    )
    (net (code "77") (name "unconnected-(U$6-IO7{slash}RTS2-PadIO7)") (class "Default")
      (node (ref "U$6") (pin "IO7") (pinfunction "IO7/RTS2_IO7") (pintype "bidirectional"))
    )
    (net (code "78") (name "unconnected-(U$6-IO19{slash}I2C2_SCL-PadIO19)") (class "Default")
      (node (ref "U$6") (pin "IO19") (pinfunction "IO19/I2C2_SCL_IO19") (pintype "bidirectional"))
    )
    (net (code "79") (name "unconnected-(U$6-IO20{slash}I2C2_SDA-PadIO20)") (class "Default")
      (node (ref "U$6") (pin "IO20") (pinfunction "IO20/I2C2_SDA_IO20") (pintype "bidirectional"))
    )
    (net (code "80") (name "unconnected-(U$6-PadADC0)") (class "Default")
      (node (ref "U$6") (pin "ADC0") (pinfunction "ADC0_ADC0") (pintype "bidirectional"))
    )
    (net (code "81") (name "unconnected-(U$6-PadADC1)") (class "Default")
      (node (ref "U$6") (pin "ADC1") (pinfunction "ADC1_ADC1") (pintype "bidirectional"))
    )
    (net (code "82") (name "unconnected-(U$6-PadHST_RX)") (class "Default")
      (node (ref "U$6") (pin "HST_RX") (pinfunction "HST_RX_HST_RX") (pintype "bidirectional"))
    )
    (net (code "83") (name "unconnected-(U$6-PadHST_TX)") (class "Default")
      (node (ref "U$6") (pin "HST_TX") (pinfunction "HST_TX_HST_TX") (pintype "bidirectional"))
    )
    (net (code "84") (name "unconnected-(U$6-PadIO14)") (class "Default")
      (node (ref "U$6") (pin "IO14") (pinfunction "IO14_IO14") (pintype "bidirectional"))
    )
    (net (code "85") (name "unconnected-(U$6-PadIO15)") (class "Default")
      (node (ref "U$6") (pin "IO15") (pinfunction "IO15_IO15") (pintype "bidirectional"))
    )
    (net (code "86") (name "unconnected-(U$6-PadIO16)") (class "Default")
      (node (ref "U$6") (pin "IO16") (pinfunction "IO16_IO16") (pintype "bidirectional"))
    )
    (net (code "87") (name "unconnected-(U$6-PadIO17)") (class "Default")
      (node (ref "U$6") (pin "IO17") (pinfunction "IO17_IO17") (pintype "bidirectional"))
    )
    (net (code "88") (name "unconnected-(U$6-PadIO18)") (class "Default")
      (node (ref "U$6") (pin "IO18") (pinfunction "IO18_IO18") (pintype "bidirectional"))
    )
    (net (code "89") (name "unconnected-(U$6-PadIO25)") (class "Default")
      (node (ref "U$6") (pin "IO25") (pinfunction "IO25_IO25") (pintype "bidirectional"))
    )
    (net (code "90") (name "unconnected-(U$6-PadIO26)") (class "Default")
      (node (ref "U$6") (pin "IO26") (pinfunction "IO26_IO26") (pintype "bidirectional"))
    )
    (net (code "91") (name "unconnected-(U$6-PadIO29)") (class "Default")
      (node (ref "U$6") (pin "IO29") (pinfunction "IO29_IO29") (pintype "bidirectional"))
    )
    (net (code "92") (name "unconnected-(U$6-PadIO30)") (class "Default")
      (node (ref "U$6") (pin "IO30") (pinfunction "IO30_IO30") (pintype "bidirectional"))
    )
    (net (code "93") (name "unconnected-(U$6-PadPWR_KEY)") (class "Default")
      (node (ref "U$6") (pin "PWR_KEY") (pinfunction "PWR_KEY_PWR_KEY") (pintype "bidirectional"))
    )
    (net (code "94") (name "unconnected-(U$6-PadVBAT)") (class "Default")
      (node (ref "U$6") (pin "VBAT") (pinfunction "VBAT_VBAT") (pintype "bidirectional"))
    )
    (net (code "95") (name "unconnected-(U$6-PadVIO)") (class "Default")
      (node (ref "U$6") (pin "VIO") (pinfunction "VIO_VIO") (pintype "bidirectional"))
    )
  )
)
